# s3.net
KiCad netlist of a schematic drawn in EasyEDA Pro
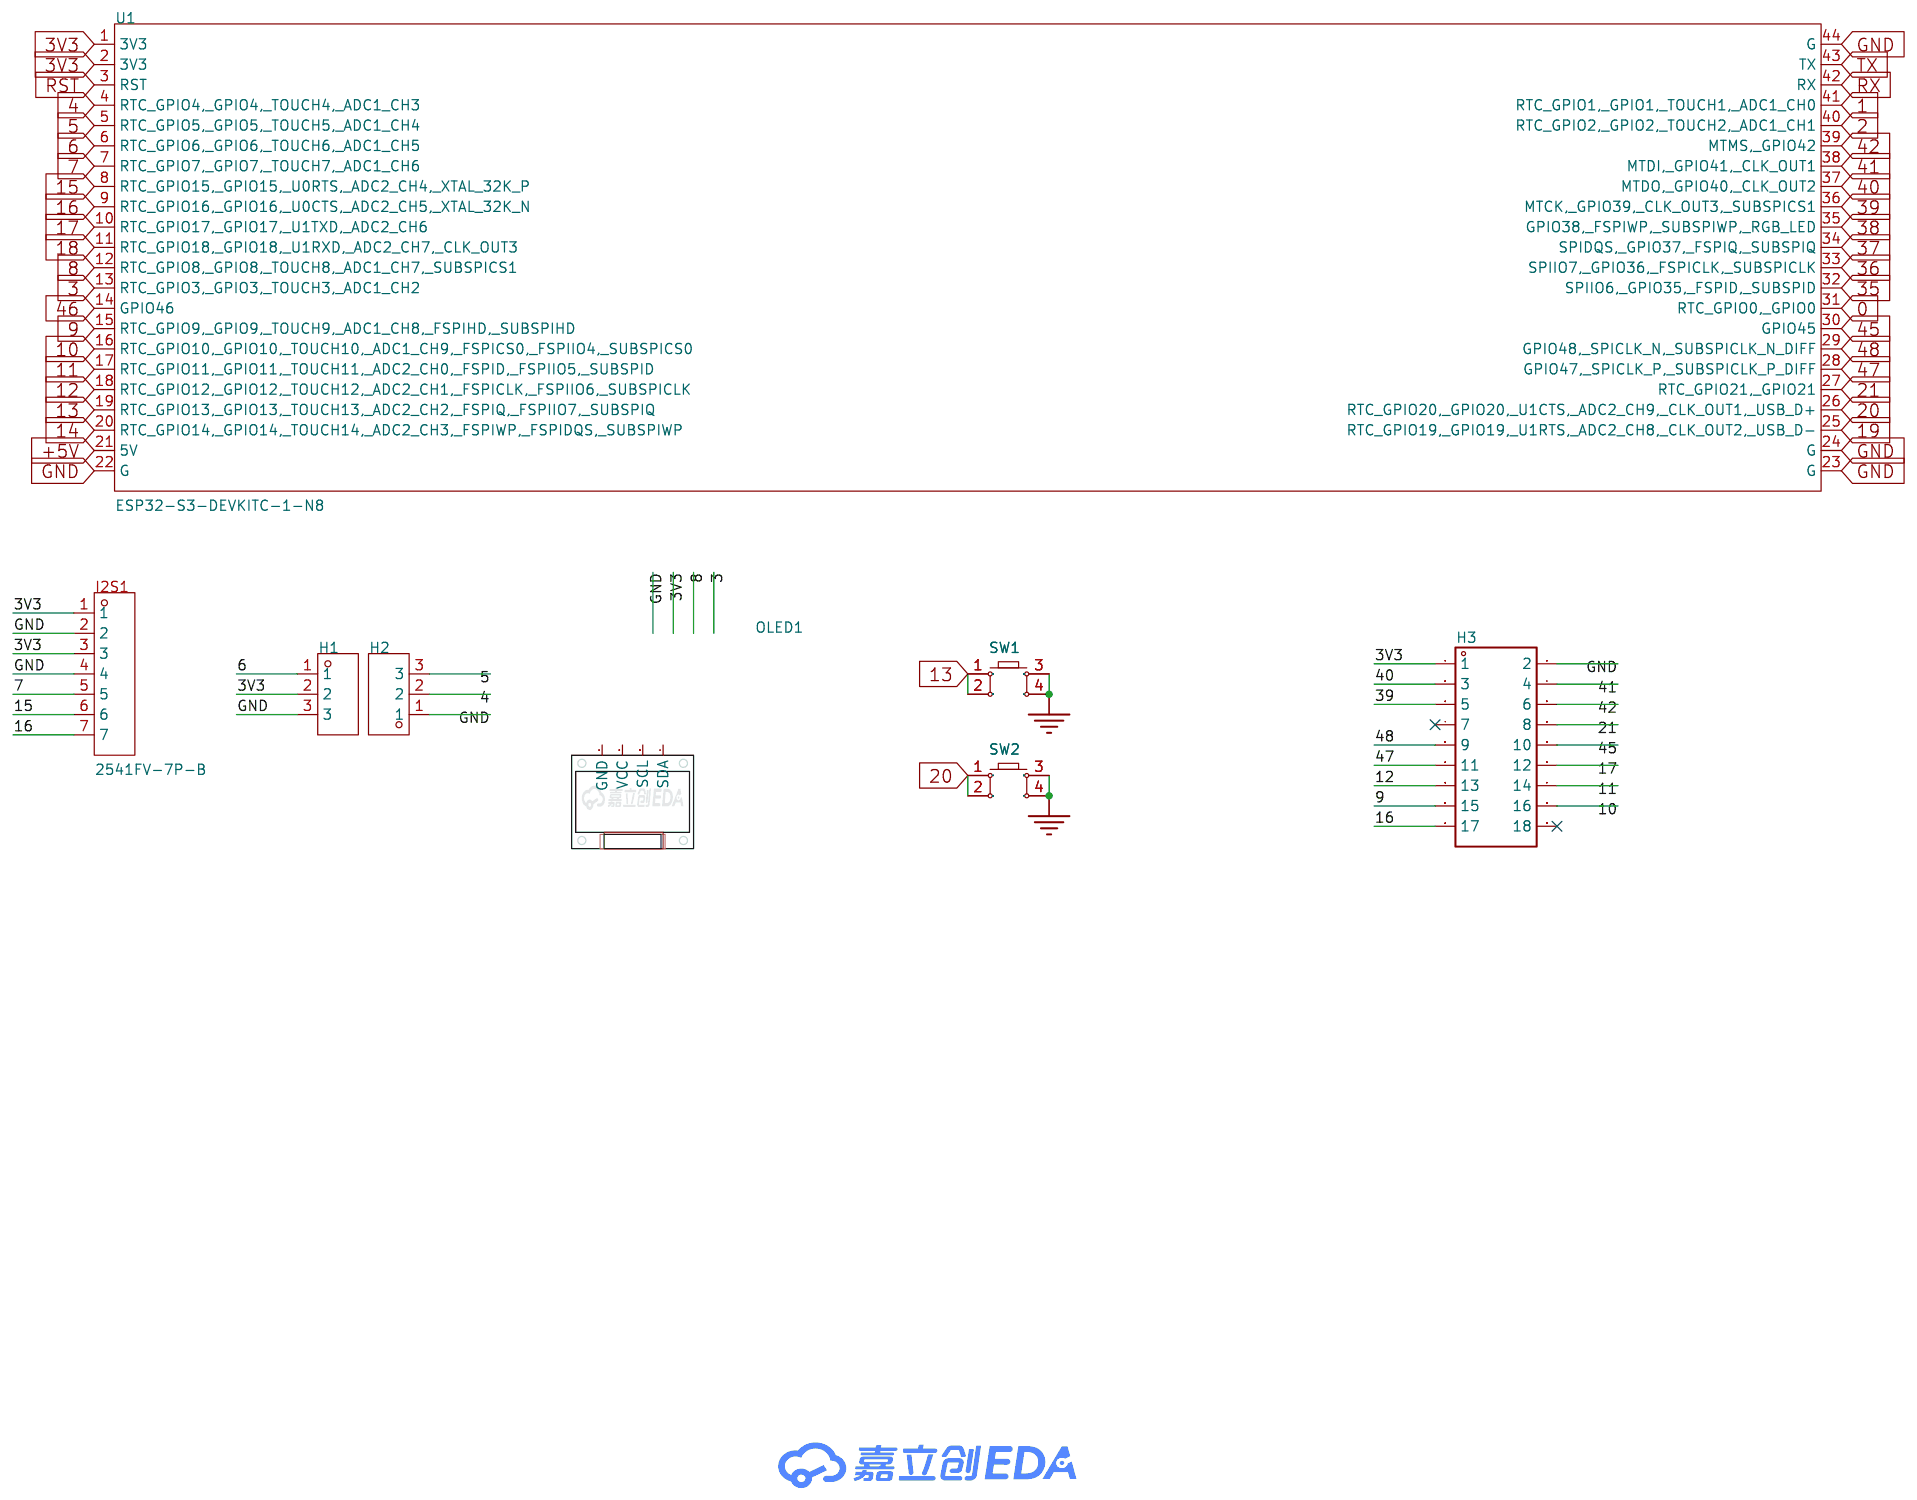
[diagram p0: schematic sheet]

(export (version "E")
  (design (tool "Eeschema 10.0.6"))
  (components
    (comp (ref "H1")
      (value "~")
      (footprint "easyedapro:HDR-TH_3P-P2.54-V-F")
      (libsource (lib "easyedapro") (part "PM254V-11-03-H85"))
    )
    (comp (ref "H2")
      (value "~")
      (footprint "easyedapro:HDR-TH_3P-P2.54-V-F")
      (libsource (lib "easyedapro") (part "PM254V-11-03-H85"))
    )
    (comp (ref "H3")
      (value "~")
      (footprint "easyedapro:HDR-TH_18P-P2.54-V-F-R2-C9-S2.54-1")
      (libsource (lib "easyedapro") (part "HDR-F-2.54_2x9"))
    )
    (comp (ref "I2S1")
      (value "2541FV-7P-B")
      (footprint "easyedapro:HDR-TH_7P-P2.54-V-F")
      (description "排母2.54mm单排 7P 直插方孔")
      (fields (field (name "Manufacturer") "HanElectricity(瀚源)"))
      (libsource (lib "easyedapro") (part "2541FV-7P-B"))
    )
    (comp (ref "OLED1")
      (value "~")
      (footprint "easyedapro:0.96OLED_4P")
      (libsource (lib "easyedapro") (part "0.96OLED模块_4P"))
    )
    (comp (ref "SW1")
      (value "~")
      (footprint "easyedapro:SW-TH_4P-L6.0-W6.0-P4.50-LS6.5")
      (libsource (lib "easyedapro") (part "轻触按键"))
    )
    (comp (ref "SW2")
      (value "~")
      (footprint "easyedapro:SW-TH_4P-L6.0-W6.0-P4.50-LS6.5")
      (libsource (lib "easyedapro") (part "轻触按键"))
    )
    (comp (ref "U1")
      (value "ESP32-S3-DEVKITC-1-N8")
      (footprint "easyedapro:CONN-TH_ESP32-S3-DEVKITC-1U-N8")
      (fields (field (name "Manufacturer") "ESPRESSIF(乐鑫)"))
      (libsource (lib "easyedapro") (part "ESP32-S3-DEVKITC-1-N8"))
    )
  )
  (nets
    (net (code "1") (name "+5V") (class "Default")
      (node (ref "U1") (pin "21") (pinfunction "5V_21") (pintype "unspecified"))
    )
    (net (code "2") (name "0") (class "Default")
      (node (ref "U1") (pin "31") (pinfunction "RTC_GPIO0,_GPIO0_31") (pintype "unspecified"))
    )
    (net (code "3") (name "1") (class "Default")
      (node (ref "U1") (pin "41") (pinfunction "RTC_GPIO1,_GPIO1,_TOUCH1,_ADC1_CH0_41") (pintype "unspecified"))
    )
    (net (code "4") (name "2") (class "Default")
      (node (ref "U1") (pin "40") (pinfunction "RTC_GPIO2,_GPIO2,_TOUCH2,_ADC1_CH1_40") (pintype "unspecified"))
    )
    (net (code "5") (name "3") (class "Default")
      (node (ref "U1") (pin "13") (pinfunction "RTC_GPIO3,_GPIO3,_TOUCH3,_ADC1_CH2_13") (pintype "unspecified"))
    )
    (net (code "6") (name "3V3") (class "Default")
      (node (ref "H1") (pin "2") (pinfunction "2_2") (pintype "unspecified"))
      (node (ref "H3") (pin "1") (pinfunction "1_1") (pintype "input"))
      (node (ref "I2S1") (pin "1") (pinfunction "1_1") (pintype "unspecified"))
      (node (ref "I2S1") (pin "3") (pinfunction "3_3") (pintype "unspecified"))
      (node (ref "U1") (pin "1") (pinfunction "3V3_1") (pintype "unspecified"))
      (node (ref "U1") (pin "2") (pinfunction "3V3_2") (pintype "unspecified"))
    )
    (net (code "7") (name "4") (class "Default")
      (node (ref "H2") (pin "2") (pinfunction "2_2") (pintype "unspecified"))
      (node (ref "U1") (pin "4") (pinfunction "RTC_GPIO4,_GPIO4,_TOUCH4,_ADC1_CH3_4") (pintype "unspecified"))
    )
    (net (code "8") (name "5") (class "Default")
      (node (ref "H2") (pin "3") (pinfunction "3_3") (pintype "unspecified"))
      (node (ref "U1") (pin "5") (pinfunction "RTC_GPIO5,_GPIO5,_TOUCH5,_ADC1_CH4_5") (pintype "unspecified"))
    )
    (net (code "9") (name "6") (class "Default")
      (node (ref "H1") (pin "1") (pinfunction "1_1") (pintype "unspecified"))
      (node (ref "U1") (pin "6") (pinfunction "RTC_GPIO6,_GPIO6,_TOUCH6,_ADC1_CH5_6") (pintype "unspecified"))
    )
    (net (code "10") (name "7") (class "Default")
      (node (ref "I2S1") (pin "5") (pinfunction "5_5") (pintype "unspecified"))
      (node (ref "U1") (pin "7") (pinfunction "RTC_GPIO7,_GPIO7,_TOUCH7,_ADC1_CH6_7") (pintype "unspecified"))
    )
    (net (code "11") (name "8") (class "Default")
      (node (ref "U1") (pin "12") (pinfunction "RTC_GPIO8,_GPIO8,_TOUCH8,_ADC1_CH7,_SUBSPICS1_12") (pintype "unspecified"))
    )
    (net (code "12") (name "9") (class "Default")
      (node (ref "H3") (pin "15") (pinfunction "15_15") (pintype "input"))
      (node (ref "U1") (pin "15") (pinfunction "RTC_GPIO9,_GPIO9,_TOUCH9,_ADC1_CH8,_FSPIHD,_SUBSPIHD_15") (pintype "unspecified"))
    )
    (net (code "13") (name "10") (class "Default")
      (node (ref "H3") (pin "16") (pinfunction "16_16") (pintype "input"))
      (node (ref "U1") (pin "16") (pinfunction "RTC_GPIO10,_GPIO10,_TOUCH10,_ADC1_CH9,_FSPICS0,_FSPIIO4,_SUBSPICS0_16") (pintype "unspecified"))
    )
    (net (code "14") (name "11") (class "Default")
      (node (ref "H3") (pin "14") (pinfunction "14_14") (pintype "input"))
      (node (ref "U1") (pin "17") (pinfunction "RTC_GPIO11,_GPIO11,_TOUCH11,_ADC2_CH0,_FSPID,_FSPIIO5,_SUBSPID_17") (pintype "unspecified"))
    )
    (net (code "15") (name "12") (class "Default")
      (node (ref "H3") (pin "13") (pinfunction "13_13") (pintype "input"))
      (node (ref "U1") (pin "18") (pinfunction "RTC_GPIO12,_GPIO12,_TOUCH12,_ADC2_CH1,_FSPICLK,_FSPIIO6,_SUBSPICLK_18") (pintype "unspecified"))
    )
    (net (code "16") (name "13") (class "Default")
      (node (ref "SW1") (pin "1") (pinfunction "1_1") (pintype "input"))
      (node (ref "SW1") (pin "2") (pinfunction "2_2") (pintype "input"))
      (node (ref "U1") (pin "19") (pinfunction "RTC_GPIO13,_GPIO13,_TOUCH13,_ADC2_CH2,_FSPIQ,_FSPIIO7,_SUBSPIQ_19") (pintype "unspecified"))
    )
    (net (code "17") (name "14") (class "Default")
      (node (ref "U1") (pin "20") (pinfunction "RTC_GPIO14,_GPIO14,_TOUCH14,_ADC2_CH3,_FSPIWP,_FSPIDQS,_SUBSPIWP_20") (pintype "unspecified"))
    )
    (net (code "18") (name "15") (class "Default")
      (node (ref "I2S1") (pin "6") (pinfunction "6_6") (pintype "unspecified"))
      (node (ref "U1") (pin "8") (pinfunction "RTC_GPIO15,_GPIO15,_U0RTS,_ADC2_CH4,_XTAL_32K_P_8") (pintype "unspecified"))
    )
    (net (code "19") (name "16") (class "Default")
      (node (ref "H3") (pin "17") (pinfunction "17_17") (pintype "input"))
      (node (ref "I2S1") (pin "7") (pinfunction "7_7") (pintype "unspecified"))
      (node (ref "U1") (pin "9") (pinfunction "RTC_GPIO16,_GPIO16,_U0CTS,_ADC2_CH5,_XTAL_32K_N_9") (pintype "unspecified"))
    )
    (net (code "20") (name "17") (class "Default")
      (node (ref "H3") (pin "12") (pinfunction "12_12") (pintype "input"))
      (node (ref "U1") (pin "10") (pinfunction "RTC_GPIO17,_GPIO17,_U1TXD,_ADC2_CH6_10") (pintype "unspecified"))
    )
    (net (code "21") (name "18") (class "Default")
      (node (ref "U1") (pin "11") (pinfunction "RTC_GPIO18,_GPIO18,_U1RXD,_ADC2_CH7,_CLK_OUT3_11") (pintype "unspecified"))
    )
    (net (code "22") (name "19") (class "Default")
      (node (ref "U1") (pin "25") (pinfunction "RTC_GPIO19,_GPIO19,_U1RTS,_ADC2_CH8,_CLK_OUT2,_USB_D-_25") (pintype "unspecified"))
    )
    (net (code "23") (name "20") (class "Default")
      (node (ref "SW2") (pin "1") (pinfunction "1_1") (pintype "input"))
      (node (ref "SW2") (pin "2") (pinfunction "2_2") (pintype "input"))
      (node (ref "U1") (pin "26") (pinfunction "RTC_GPIO20,_GPIO20,_U1CTS,_ADC2_CH9,_CLK_OUT1,_USB_D+_26") (pintype "unspecified"))
    )
    (net (code "24") (name "21") (class "Default")
      (node (ref "H3") (pin "8") (pinfunction "8_8") (pintype "input"))
      (node (ref "U1") (pin "27") (pinfunction "RTC_GPIO21,_GPIO21_27") (pintype "unspecified"))
    )
    (net (code "25") (name "35") (class "Default")
      (node (ref "U1") (pin "32") (pinfunction "SPIIO6,_GPIO35,_FSPID,_SUBSPID_32") (pintype "unspecified"))
    )
    (net (code "26") (name "36") (class "Default")
      (node (ref "U1") (pin "33") (pinfunction "SPIIO7,_GPIO36,_FSPICLK,_SUBSPICLK_33") (pintype "unspecified"))
    )
    (net (code "27") (name "37") (class "Default")
      (node (ref "U1") (pin "34") (pinfunction "SPIDQS,_GPIO37,_FSPIQ,_SUBSPIQ_34") (pintype "unspecified"))
    )
    (net (code "28") (name "38") (class "Default")
      (node (ref "U1") (pin "35") (pinfunction "GPIO38,_FSPIWP,_SUBSPIWP,_RGB_LED_35") (pintype "unspecified"))
    )
    (net (code "29") (name "39") (class "Default")
      (node (ref "H3") (pin "5") (pinfunction "5_5") (pintype "input"))
      (node (ref "U1") (pin "36") (pinfunction "MTCK,_GPIO39,_CLK_OUT3,_SUBSPICS1_36") (pintype "unspecified"))
    )
    (net (code "30") (name "40") (class "Default")
      (node (ref "H3") (pin "3") (pinfunction "3_3") (pintype "input"))
      (node (ref "U1") (pin "37") (pinfunction "MTDO,_GPIO40,_CLK_OUT2_37") (pintype "unspecified"))
    )
    (net (code "31") (name "41") (class "Default")
      (node (ref "H3") (pin "4") (pinfunction "4_4") (pintype "input"))
      (node (ref "U1") (pin "38") (pinfunction "MTDI,_GPIO41,_CLK_OUT1_38") (pintype "unspecified"))
    )
    (net (code "32") (name "42") (class "Default")
      (node (ref "H3") (pin "6") (pinfunction "6_6") (pintype "input"))
      (node (ref "U1") (pin "39") (pinfunction "MTMS,_GPIO42_39") (pintype "unspecified"))
    )
    (net (code "33") (name "45") (class "Default")
      (node (ref "H3") (pin "10") (pinfunction "10_10") (pintype "input"))
      (node (ref "U1") (pin "30") (pinfunction "GPIO45_30") (pintype "unspecified"))
    )
    (net (code "34") (name "46") (class "Default")
      (node (ref "U1") (pin "14") (pinfunction "GPIO46_14") (pintype "unspecified"))
    )
    (net (code "35") (name "47") (class "Default")
      (node (ref "H3") (pin "11") (pinfunction "11_11") (pintype "input"))
      (node (ref "U1") (pin "28") (pinfunction "GPIO47,_SPICLK_P,_SUBSPICLK_P_DIFF_28") (pintype "unspecified"))
    )
    (net (code "36") (name "48") (class "Default")
      (node (ref "H3") (pin "9") (pinfunction "9_9") (pintype "input"))
      (node (ref "U1") (pin "29") (pinfunction "GPIO48,_SPICLK_N,_SUBSPICLK_N_DIFF_29") (pintype "unspecified"))
    )
    (net (code "37") (name "GND") (class "Default")
      (node (ref "H1") (pin "3") (pinfunction "3_3") (pintype "unspecified"))
      (node (ref "H2") (pin "1") (pinfunction "1_1") (pintype "unspecified"))
      (node (ref "H3") (pin "2") (pinfunction "2_2") (pintype "input"))
      (node (ref "I2S1") (pin "2") (pinfunction "2_2") (pintype "unspecified"))
      (node (ref "I2S1") (pin "4") (pinfunction "4_4") (pintype "unspecified"))
      (node (ref "SW1") (pin "3") (pinfunction "3_3") (pintype "input"))
      (node (ref "SW1") (pin "4") (pinfunction "4_4") (pintype "input"))
      (node (ref "SW2") (pin "3") (pinfunction "3_3") (pintype "input"))
      (node (ref "SW2") (pin "4") (pinfunction "4_4") (pintype "input"))
      (node (ref "U1") (pin "22") (pinfunction "G_22") (pintype "unspecified"))
      (node (ref "U1") (pin "23") (pinfunction "G_23") (pintype "unspecified"))
      (node (ref "U1") (pin "24") (pinfunction "G_24") (pintype "unspecified"))
      (node (ref "U1") (pin "44") (pinfunction "G_44") (pintype "unspecified"))
    )
    (net (code "38") (name "RST") (class "Default")
      (node (ref "U1") (pin "3") (pinfunction "RST_3") (pintype "unspecified"))
    )
    (net (code "39") (name "RX") (class "Default")
      (node (ref "U1") (pin "42") (pinfunction "RX_42") (pintype "unspecified"))
    )
    (net (code "40") (name "TX") (class "Default")
      (node (ref "U1") (pin "43") (pinfunction "TX_43") (pintype "unspecified"))
    )
    (net (code "41") (name "unconnected-(H3-Pad7)") (class "Default")
      (node (ref "H3") (pin "7") (pinfunction "7_7") (pintype "input+no_connect"))
    )
    (net (code "42") (name "unconnected-(H3-Pad18)") (class "Default")
      (node (ref "H3") (pin "18") (pinfunction "18_18") (pintype "input+no_connect"))
    )
    (net (code "43") (name "unconnected-(OLED1-GND-Pad1)") (class "Default")
      (node (ref "OLED1") (pin "1") (pinfunction "GND_1") (pintype "input"))
    )
    (net (code "44") (name "unconnected-(OLED1-SCL-Pad3)") (class "Default")
      (node (ref "OLED1") (pin "3") (pinfunction "SCL_3") (pintype "input"))
    )
    (net (code "45") (name "unconnected-(OLED1-SDA-Pad4)") (class "Default")
      (node (ref "OLED1") (pin "4") (pinfunction "SDA_4") (pintype "input"))
    )
    (net (code "46") (name "unconnected-(OLED1-VCC-Pad2)") (class "Default")
      (node (ref "OLED1") (pin "2") (pinfunction "VCC_2") (pintype "input"))
    )
  )
)
